# 0127_microphone_type_J_102.net
KiCad netlist of a schematic drawn in EAGLE
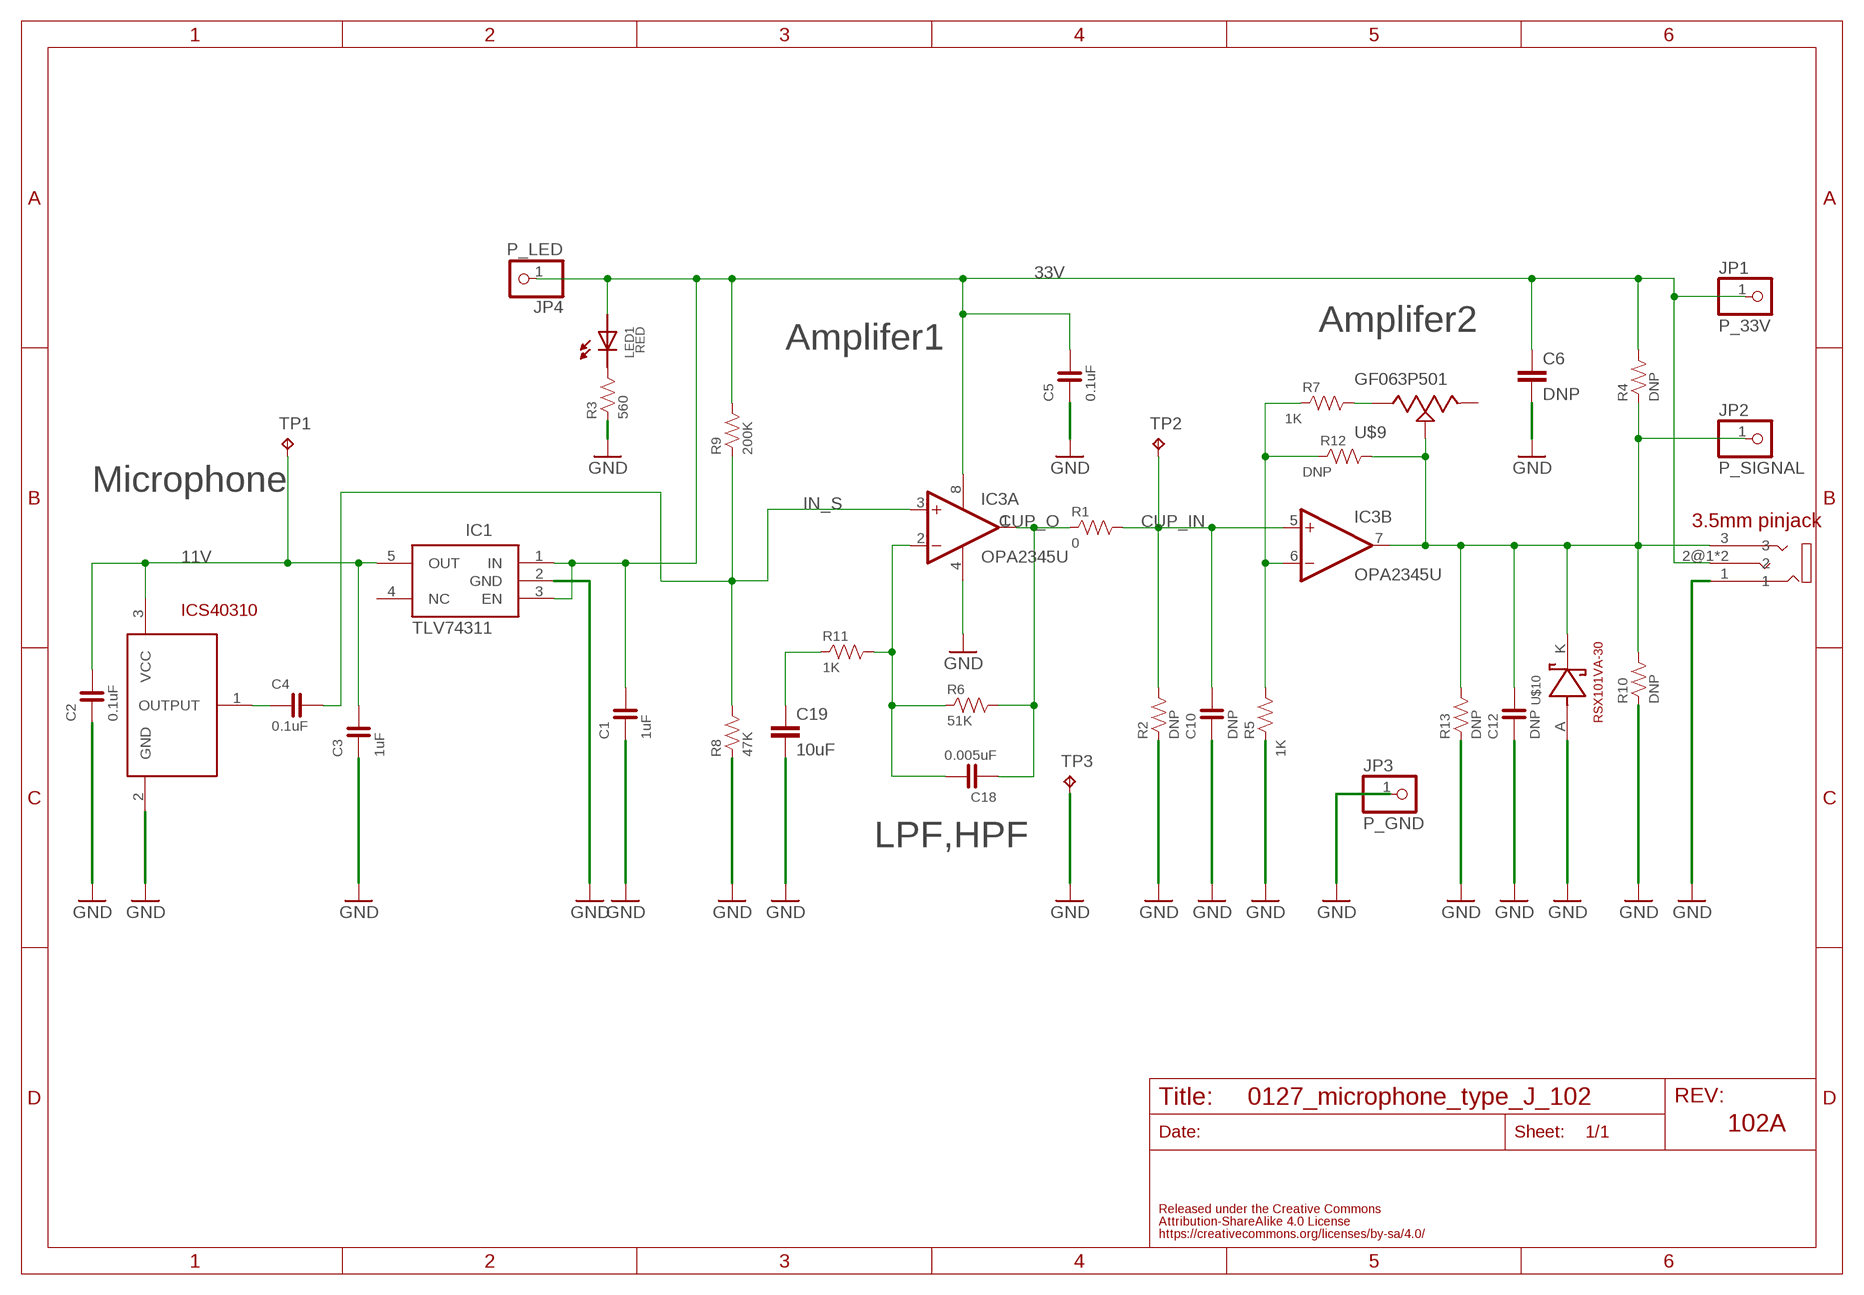
[diagram p0: schematic, sheet 1]

(export (version "E")
  (design (tool "Eeschema 10.0.6"))
  (components
    (comp (ref "C1")
      (value "1uF")
      (footprint "eagle-import:0603")
      (libsource (lib "eagle-import") (part "CAPACITOR-0603"))
    )
    (comp (ref "C2")
      (value "0.1uF")
      (footprint "eagle-import:0603")
      (libsource (lib "eagle-import") (part "CAPACITOR-0603"))
    )
    (comp (ref "C3")
      (value "1uF")
      (footprint "eagle-import:0603")
      (libsource (lib "eagle-import") (part "CAPACITOR-0603"))
    )
    (comp (ref "C4")
      (value "0.1uF")
      (footprint "eagle-import:0603")
      (libsource (lib "eagle-import") (part "CAPACITOR-0603"))
    )
    (comp (ref "C5")
      (value "0.1uF")
      (footprint "eagle-import:0603")
      (libsource (lib "eagle-import") (part "CAPACITOR-0603"))
    )
    (comp (ref "C6")
      (value "DNP")
      (footprint "eagle-import:C1206K")
      (libsource (lib "eagle-import") (part "C-EUC1206K"))
    )
    (comp (ref "C10")
      (value "DNP")
      (footprint "eagle-import:0603")
      (fields (field (name "SPICEPREFIX") "C"))
      (libsource (lib "eagle-import") (part "CAPACITOR-0603"))
    )
    (comp (ref "C12")
      (value "DNP")
      (footprint "eagle-import:0603")
      (fields (field (name "SPICEPREFIX") "C"))
      (libsource (lib "eagle-import") (part "CAPACITOR-0603"))
    )
    (comp (ref "C18")
      (value "0.005uF")
      (footprint "eagle-import:0603")
      (libsource (lib "eagle-import") (part "CAPACITOR-0603"))
    )
    (comp (ref "C19")
      (value "10uF")
      (footprint "eagle-import:C1206K")
      (libsource (lib "eagle-import") (part "C-EUC1206K"))
    )
    (comp (ref "IC1")
      (value "TLV74311")
      (footprint "eagle-import:SOT-23-5")
      (libsource (lib "eagle-import") (part "TLV74311"))
    )
    (comp (ref "IC3")
      (value "OPA2345U")
      (footprint "eagle-import:SO08")
      (libsource (lib "eagle-import") (part "OPA2U345"))
    )
    (comp (ref "ICS40310")
      (value "ANALOG-MICICS40310")
      (footprint "eagle-import:ICS40310")
      (libsource (lib "eagle-import") (part "ANALOG-MICICS40310"))
    )
    (comp (ref "JP1")
      (value "P_33V")
      (footprint "eagle-import:1X01")
      (libsource (lib "eagle-import") (part "PINHD-1X1"))
    )
    (comp (ref "JP2")
      (value "P_SIGNAL")
      (footprint "eagle-import:1X01")
      (libsource (lib "eagle-import") (part "PINHD-1X1"))
    )
    (comp (ref "JP3")
      (value "P_GND")
      (footprint "eagle-import:1X01")
      (libsource (lib "eagle-import") (part "PINHD-1X1"))
    )
    (comp (ref "JP4")
      (value "P_LED")
      (footprint "eagle-import:1X01")
      (libsource (lib "eagle-import") (part "PINHD-1X1"))
    )
    (comp (ref "LED1")
      (value "RED")
      (footprint "eagle-import:0603-NARROW")
      (libsource (lib "eagle-import") (part "LED-0603-NARROW"))
    )
    (comp (ref "R1")
      (value "0")
      (footprint "eagle-import:0603")
      (libsource (lib "eagle-import") (part "RESISTOR-0603"))
    )
    (comp (ref "R2")
      (value "DNP")
      (footprint "eagle-import:0603")
      (libsource (lib "eagle-import") (part "RESISTOR-0603"))
    )
    (comp (ref "R3")
      (value "560")
      (footprint "eagle-import:0603")
      (libsource (lib "eagle-import") (part "RESISTOR-0603"))
    )
    (comp (ref "R4")
      (value "DNP")
      (footprint "eagle-import:0603")
      (libsource (lib "eagle-import") (part "RESISTOR-0603"))
    )
    (comp (ref "R5")
      (value "1K")
      (footprint "eagle-import:0603")
      (libsource (lib "eagle-import") (part "RESISTOR-0603"))
    )
    (comp (ref "R6")
      (value "51K")
      (footprint "eagle-import:0603")
      (libsource (lib "eagle-import") (part "RESISTOR-0603"))
    )
    (comp (ref "R7")
      (value "1K")
      (footprint "eagle-import:0603")
      (libsource (lib "eagle-import") (part "RESISTOR-0603"))
    )
    (comp (ref "R8")
      (value "47K")
      (footprint "eagle-import:0603")
      (libsource (lib "eagle-import") (part "RESISTOR-0603"))
    )
    (comp (ref "R9")
      (value "200K")
      (footprint "eagle-import:0603")
      (libsource (lib "eagle-import") (part "RESISTOR-0603"))
    )
    (comp (ref "R10")
      (value "DNP")
      (footprint "eagle-import:0603")
      (libsource (lib "eagle-import") (part "RESISTOR-0603"))
    )
    (comp (ref "R11")
      (value "1K")
      (footprint "eagle-import:0603")
      (libsource (lib "eagle-import") (part "RESISTOR-0603"))
    )
    (comp (ref "R12")
      (value "DNP")
      (footprint "eagle-import:0603")
      (libsource (lib "eagle-import") (part "RESISTOR-0603"))
    )
    (comp (ref "R13")
      (value "DNP")
      (footprint "eagle-import:0603")
      (libsource (lib "eagle-import") (part "RESISTOR-0603"))
    )
    (comp (ref "TP1")
      (value "TPB1,27")
      (footprint "eagle-import:B1,27")
      (libsource (lib "eagle-import") (part "TPB1,27"))
    )
    (comp (ref "TP2")
      (value "TPB1,27")
      (footprint "eagle-import:B1,27")
      (libsource (lib "eagle-import") (part "TPB1,27"))
    )
    (comp (ref "TP3")
      (value "TPB1,27")
      (footprint "eagle-import:B1,27")
      (libsource (lib "eagle-import") (part "TPB1,27"))
    )
    (comp (ref "U$9")
      (value "GF063P501")
      (footprint "eagle-import:GF063P103")
      (libsource (lib "eagle-import") (part "GF063P501"))
    )
    (comp (ref "U$10")
      (value "RSX101VA-30")
      (footprint "eagle-import:RSX101VA-30")
      (libsource (lib "eagle-import") (part "RSX101VA-30"))
    )
    (comp (ref "U$11")
      (value "MJ8435")
      (footprint "eagle-import:MJ8435")
      (libsource (lib "eagle-import") (part "MJ8435"))
    )
  )
  (nets
    (net (code "1") (name "/11V") (class "Default")
      (node (ref "C2") (pin "2") (pinfunction "2_2") (pintype "passive"))
      (node (ref "C3") (pin "2") (pinfunction "2_2") (pintype "passive"))
      (node (ref "IC1") (pin "5") (pinfunction "OUT_5") (pintype "bidirectional"))
      (node (ref "ICS40310") (pin "3") (pinfunction "VCC_3") (pintype "bidirectional"))
      (node (ref "TP1") (pin "TP") (pinfunction "TP_TP") (pintype "input"))
    )
    (net (code "2") (name "/33V") (class "Default")
      (node (ref "C1") (pin "2") (pinfunction "2_2") (pintype "passive"))
      (node (ref "C5") (pin "2") (pinfunction "2_2") (pintype "passive"))
      (node (ref "C6") (pin "1") (pinfunction "1_1") (pintype "passive"))
      (node (ref "IC1") (pin "1") (pinfunction "IN_1") (pintype "input"))
      (node (ref "IC1") (pin "3") (pinfunction "EN_3") (pintype "input"))
      (node (ref "IC3") (pin "8") (pinfunction "V+_8") (pintype "power_in"))
      (node (ref "JP1") (pin "1") (pinfunction "1_1") (pintype "passive"))
      (node (ref "JP4") (pin "1") (pinfunction "1_1") (pintype "passive"))
      (node (ref "LED1") (pin "ANODE") (pinfunction "ANODE_ANODE") (pintype "passive"))
      (node (ref "R4") (pin "2") (pinfunction "2_2") (pintype "bidirectional"))
      (node (ref "R9") (pin "2") (pinfunction "2_2") (pintype "bidirectional"))
      (node (ref "U$11") (pin "2@1") (pinfunction "2_2@1") (pintype "bidirectional"))
      (node (ref "U$11") (pin "2@2") (pinfunction "2_2@2") (pintype "bidirectional"))
    )
    (net (code "3") (name "/CUP_IN") (class "Default")
      (node (ref "C10") (pin "2") (pinfunction "2_2") (pintype "passive"))
      (node (ref "IC3") (pin "5") (pinfunction "+IN_5") (pintype "input"))
      (node (ref "R1") (pin "2") (pinfunction "2_2") (pintype "bidirectional"))
      (node (ref "R2") (pin "2") (pinfunction "2_2") (pintype "bidirectional"))
      (node (ref "TP2") (pin "TP") (pinfunction "TP_TP") (pintype "input"))
    )
    (net (code "4") (name "/CUP_O") (class "Default")
      (node (ref "C18") (pin "1") (pinfunction "1_1") (pintype "passive"))
      (node (ref "IC3") (pin "1") (pinfunction "OUT_1") (pintype "output"))
      (node (ref "R1") (pin "1") (pinfunction "1_1") (pintype "bidirectional"))
      (node (ref "R6") (pin "2") (pinfunction "2_2") (pintype "bidirectional"))
    )
    (net (code "5") (name "/IN_S") (class "Default")
      (node (ref "C4") (pin "2") (pinfunction "2_2") (pintype "passive"))
      (node (ref "IC3") (pin "3") (pinfunction "+IN_3") (pintype "input"))
      (node (ref "R8") (pin "2") (pinfunction "2_2") (pintype "bidirectional"))
      (node (ref "R9") (pin "1") (pinfunction "1_1") (pintype "bidirectional"))
    )
    (net (code "6") (name "GND") (class "Default")
      (node (ref "C1") (pin "1") (pinfunction "1_1") (pintype "passive"))
      (node (ref "C10") (pin "1") (pinfunction "1_1") (pintype "passive"))
      (node (ref "C12") (pin "1") (pinfunction "1_1") (pintype "passive"))
      (node (ref "C19") (pin "2") (pinfunction "2_2") (pintype "passive"))
      (node (ref "C2") (pin "1") (pinfunction "1_1") (pintype "passive"))
      (node (ref "C3") (pin "1") (pinfunction "1_1") (pintype "passive"))
      (node (ref "C5") (pin "1") (pinfunction "1_1") (pintype "passive"))
      (node (ref "C6") (pin "2") (pinfunction "2_2") (pintype "passive"))
      (node (ref "IC1") (pin "2") (pinfunction "GND_2") (pintype "power_in"))
      (node (ref "IC3") (pin "4") (pinfunction "V-_4") (pintype "power_in"))
      (node (ref "ICS40310") (pin "2") (pinfunction "GND_2") (pintype "bidirectional"))
      (node (ref "JP3") (pin "1") (pinfunction "1_1") (pintype "passive"))
      (node (ref "R10") (pin "1") (pinfunction "1_1") (pintype "bidirectional"))
      (node (ref "R13") (pin "1") (pinfunction "1_1") (pintype "bidirectional"))
      (node (ref "R2") (pin "1") (pinfunction "1_1") (pintype "bidirectional"))
      (node (ref "R3") (pin "1") (pinfunction "1_1") (pintype "bidirectional"))
      (node (ref "R5") (pin "1") (pinfunction "1_1") (pintype "bidirectional"))
      (node (ref "R8") (pin "1") (pinfunction "1_1") (pintype "bidirectional"))
      (node (ref "TP3") (pin "TP") (pinfunction "TP_TP") (pintype "input"))
      (node (ref "U$10") (pin "A") (pinfunction "ANODE_A") (pintype "bidirectional"))
      (node (ref "U$11") (pin "1") (pinfunction "1_1") (pintype "bidirectional"))
    )
    (net (code "7") (name "Net-(C19-Pad1)") (class "Default")
      (node (ref "C19") (pin "1") (pinfunction "1_1") (pintype "passive"))
      (node (ref "R11") (pin "1") (pinfunction "1_1") (pintype "bidirectional"))
    )
    (net (code "8") (name "Net-(IC3A--IN)") (class "Default")
      (node (ref "C18") (pin "2") (pinfunction "2_2") (pintype "passive"))
      (node (ref "IC3") (pin "2") (pinfunction "-IN_2") (pintype "input"))
      (node (ref "R11") (pin "2") (pinfunction "2_2") (pintype "bidirectional"))
      (node (ref "R6") (pin "1") (pinfunction "1_1") (pintype "bidirectional"))
    )
    (net (code "9") (name "Net-(IC3B--IN)") (class "Default")
      (node (ref "IC3") (pin "6") (pinfunction "-IN_6") (pintype "input"))
      (node (ref "R12") (pin "1") (pinfunction "1_1") (pintype "bidirectional"))
      (node (ref "R5") (pin "2") (pinfunction "2_2") (pintype "bidirectional"))
      (node (ref "R7") (pin "1") (pinfunction "1_1") (pintype "bidirectional"))
    )
    (net (code "10") (name "Net-(IC3B-OUT)") (class "Default")
      (node (ref "C12") (pin "2") (pinfunction "2_2") (pintype "passive"))
      (node (ref "IC3") (pin "7") (pinfunction "OUT_7") (pintype "output"))
      (node (ref "JP2") (pin "1") (pinfunction "1_1") (pintype "passive"))
      (node (ref "R10") (pin "2") (pinfunction "2_2") (pintype "bidirectional"))
      (node (ref "R12") (pin "2") (pinfunction "2_2") (pintype "bidirectional"))
      (node (ref "R13") (pin "2") (pinfunction "2_2") (pintype "bidirectional"))
      (node (ref "R4") (pin "1") (pinfunction "1_1") (pintype "bidirectional"))
      (node (ref "U$10") (pin "K") (pinfunction "CATHODE_K") (pintype "bidirectional"))
      (node (ref "U$11") (pin "3") (pinfunction "3_3") (pintype "bidirectional"))
      (node (ref "U$9") (pin "2") (pinfunction "2_2") (pintype "passive"))
    )
    (net (code "11") (name "Net-(ICS40310-OUTPUT)") (class "Default")
      (node (ref "C4") (pin "1") (pinfunction "1_1") (pintype "passive"))
      (node (ref "ICS40310") (pin "1") (pinfunction "OUTPUT_1") (pintype "bidirectional"))
    )
    (net (code "12") (name "Net-(LED1-PadCATHODE)") (class "Default")
      (node (ref "LED1") (pin "CATHODE") (pinfunction "CATHODE_CATHODE") (pintype "passive"))
      (node (ref "R3") (pin "2") (pinfunction "2_2") (pintype "bidirectional"))
    )
    (net (code "13") (name "Net-(R7-Pad2)") (class "Default")
      (node (ref "R7") (pin "2") (pinfunction "2_2") (pintype "bidirectional"))
      (node (ref "U$9") (pin "3") (pinfunction "3_3") (pintype "passive"))
    )
    (net (code "14") (name "unconnected-(IC1-NC-Pad4)") (class "Default")
      (node (ref "IC1") (pin "4") (pinfunction "NC_4") (pintype "no_connect"))
    )
    (net (code "15") (name "unconnected-(U$9-Pad1)") (class "Default")
      (node (ref "U$9") (pin "1") (pinfunction "1_1") (pintype "passive"))
    )
  )
)
